# OTH002.net
KiCad netlist of a schematic drawn in Altium Designer
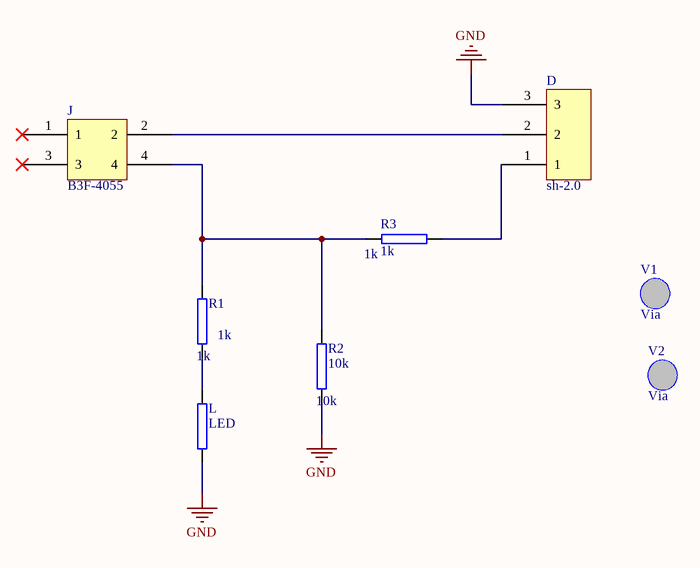
[diagram p0: OTH002.SchDoc]

(export (version "E")
  (design (tool "Eeschema 10.0.6"))
  (components
    (comp (ref "D") (value "sh-2.0") (footprint "sh-2.0") (libsource (lib "zhangchong") (part "sh-2.0")))
    (comp (ref "J") (value "B3F-4055") (footprint "B3F") (libsource (lib "zhangchong") (part "B3F-4055")))
    (comp (ref "L") (value "LED") (footprint "0402") (libsource (lib "gupeng_sch") (part "RES0402")))
    (comp (ref "R1")
      (value "1k")
      (footprint "0402")
      (fields (field (name "ALTIUM_UNNAMED_1") "1k"))
      (libsource (lib "gupeng_sch") (part "RES0402"))
    )
    (comp (ref "R2")
      (value "10k")
      (footprint "0402")
      (fields (field (name "ALTIUM_UNNAMED_1") "10k"))
      (libsource (lib "gupeng_sch") (part "RES0402"))
    )
    (comp (ref "R3")
      (value "1k")
      (footprint "0402")
      (fields (field (name "ALTIUM_UNNAMED_1") "1k"))
      (libsource (lib "gupeng_sch") (part "RES0402"))
    )
    (comp (ref "V1") (value "Via") (footprint "zhaoyujiu:Via") (libsource (lib "zhaoyujiu") (part "Via")))
    (comp (ref "V2") (value "Via") (footprint "zhaoyujiu:Via") (libsource (lib "zhaoyujiu") (part "Via")))
  )
  (nets
    (net (code "1") (name "GND") (class "Default")
      (node (ref "D") (pin "3") (pinfunction "3_3") (pintype "passive"))
      (node (ref "L") (pin "1") (pinfunction "1_1") (pintype "passive"))
      (node (ref "R2") (pin "1") (pinfunction "1_1") (pintype "passive"))
    )
    (net (code "2") (name "Net-(D-Pad1)") (class "Default")
      (node (ref "D") (pin "1") (pinfunction "1_1") (pintype "passive"))
      (node (ref "R3") (pin "2") (pinfunction "2_2") (pintype "passive"))
    )
    (net (code "3") (name "Net-(D-Pad2)") (class "Default")
      (node (ref "D") (pin "2") (pinfunction "2_2") (pintype "passive"))
      (node (ref "J") (pin "2") (pinfunction "2_2") (pintype "passive"))
    )
    (net (code "4") (name "Net-(J-Pad4)") (class "Default")
      (node (ref "J") (pin "4") (pinfunction "4_4") (pintype "passive"))
      (node (ref "R1") (pin "2") (pinfunction "2_2") (pintype "passive"))
      (node (ref "R2") (pin "2") (pinfunction "2_2") (pintype "passive"))
      (node (ref "R3") (pin "1") (pinfunction "1_1") (pintype "passive"))
    )
    (net (code "5") (name "Net-(L-Pad2)") (class "Default")
      (node (ref "L") (pin "2") (pinfunction "2_2") (pintype "passive"))
      (node (ref "R1") (pin "1") (pinfunction "1_1") (pintype "passive"))
    )
    (net (code "6") (name "unconnected-(J-Pad1)") (class "Default")
      (node (ref "J") (pin "1") (pinfunction "1_1") (pintype "passive+no_connect"))
    )
    (net (code "7") (name "unconnected-(J-Pad3)") (class "Default")
      (node (ref "J") (pin "3") (pinfunction "3_3") (pintype "passive+no_connect"))
    )
  )
)
